# MyProSch2.net
KiCad netlist of a schematic drawn in Altium Designer
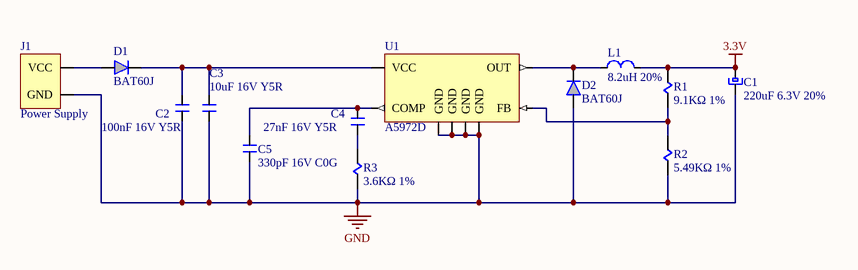
[diagram p0: MyProSch2.SchDoc]

(export (version "E")
  (design (tool "Eeschema 10.0.6"))
  (components
    (comp (ref "C1") (value "220uF 6.3V 20%") (libsource (lib "MyPro") (part "Polarized Capacitor")))
    (comp (ref "C2")
      (value "100nF 16V Y5R")
      (description "Capacitor")
      (libsource (lib "MyPro") (part "Capacitor"))
    )
    (comp (ref "C3")
      (value "10uF 16V Y5R")
      (description "Capacitor")
      (libsource (lib "MyPro") (part "Capacitor"))
    )
    (comp (ref "C4")
      (value "27nF 16V Y5R")
      (description "Capacitor")
      (libsource (lib "MyPro") (part "Capacitor"))
    )
    (comp (ref "C5")
      (value "330pF 16V C0G")
      (description "Capacitor")
      (libsource (lib "MyPro") (part "Capacitor"))
    )
    (comp (ref "D1") (value "BAT60J") (description "Generic Diode") (libsource (lib "MyPro") (part "Diode")))
    (comp (ref "D2") (value "BAT60J") (description "Generic Diode") (libsource (lib "MyPro") (part "Diode")))
    (comp (ref "J1") (value "Power Supply") (libsource (lib "MyPro") (part "Power Connector")))
    (comp (ref "L1") (value "8.2uH 20%") (description "Inductor") (libsource (lib "MyPro") (part "Inductor")))
    (comp (ref "R1") (value "9.1KΩ 1%") (description "Resistor") (libsource (lib "MyPro") (part "Resistor")))
    (comp (ref "R2") (value "5.49KΩ 1%") (description "Resistor") (libsource (lib "MyPro") (part "Resistor")))
    (comp (ref "R3") (value "3.6KΩ 1%") (description "Resistor") (libsource (lib "MyPro") (part "Resistor")))
    (comp (ref "U1")
      (value "A5972D")
      (description "Fuente Switching 3.3v 1.5A")
      (libsource (lib "MyPro") (part "A5972D"))
    )
  )
  (nets
    (net (code "1") (name "3.3V") (class "Default")
      (node (ref "C1") (pin "1") (pinfunction "P_1") (pintype "passive"))
      (node (ref "L1") (pin "2") (pinfunction "P2_2") (pintype "passive"))
      (node (ref "R1") (pin "2") (pinfunction "P2_2") (pintype "passive"))
    )
    (net (code "2") (name "GND") (class "Default")
      (node (ref "C1") (pin "2") (pinfunction "N_2") (pintype "passive"))
      (node (ref "C2") (pin "2") (pinfunction "A2_2") (pintype "passive"))
      (node (ref "C3") (pin "2") (pinfunction "A2_2") (pintype "passive"))
      (node (ref "C5") (pin "2") (pinfunction "A2_2") (pintype "passive"))
      (node (ref "D2") (pin "1") (pinfunction "A_1") (pintype "passive"))
      (node (ref "J1") (pin "2") (pinfunction "GND_2") (pintype "passive"))
      (node (ref "R2") (pin "1") (pinfunction "P1_1") (pintype "passive"))
      (node (ref "R3") (pin "1") (pinfunction "P1_1") (pintype "passive"))
      (node (ref "U1") (pin "2") (pinfunction "GND_2") (pintype "passive"))
      (node (ref "U1") (pin "3") (pinfunction "GND_3") (pintype "passive"))
      (node (ref "U1") (pin "6") (pinfunction "GND_6") (pintype "passive"))
      (node (ref "U1") (pin "7") (pinfunction "GND_7") (pintype "passive"))
    )
    (net (code "3") (name "Net-(C2-A1)") (class "Default")
      (node (ref "C2") (pin "1") (pinfunction "A1_1") (pintype "passive"))
      (node (ref "C3") (pin "1") (pinfunction "A1_1") (pintype "passive"))
      (node (ref "D1") (pin "2") (pinfunction "K_2") (pintype "passive"))
      (node (ref "U1") (pin "8") (pinfunction "VCC_8") (pintype "passive"))
    )
    (net (code "4") (name "Net-(C4-A1)") (class "Default")
      (node (ref "C4") (pin "1") (pinfunction "A1_1") (pintype "passive"))
      (node (ref "C5") (pin "1") (pinfunction "A1_1") (pintype "passive"))
      (node (ref "U1") (pin "4") (pinfunction "COMP_4") (pintype "output"))
    )
    (net (code "5") (name "Net-(C4-A2)") (class "Default")
      (node (ref "C4") (pin "2") (pinfunction "A2_2") (pintype "passive"))
      (node (ref "R3") (pin "2") (pinfunction "P2_2") (pintype "passive"))
    )
    (net (code "6") (name "Net-(D1-A)") (class "Default")
      (node (ref "D1") (pin "1") (pinfunction "A_1") (pintype "passive"))
      (node (ref "J1") (pin "1") (pinfunction "VCC_1") (pintype "passive"))
    )
    (net (code "7") (name "Net-(D2-K)") (class "Default")
      (node (ref "D2") (pin "2") (pinfunction "K_2") (pintype "passive"))
      (node (ref "L1") (pin "1") (pinfunction "P1_1") (pintype "passive"))
      (node (ref "U1") (pin "1") (pinfunction "OUT_1") (pintype "output"))
    )
    (net (code "8") (name "Net-(R1-P1)") (class "Default")
      (node (ref "R1") (pin "1") (pinfunction "P1_1") (pintype "passive"))
      (node (ref "R2") (pin "2") (pinfunction "P2_2") (pintype "passive"))
      (node (ref "U1") (pin "5") (pinfunction "FB_5") (pintype "input"))
    )
  )
)
